# develboard.net
KiCad netlist of a schematic drawn in Altium Designer
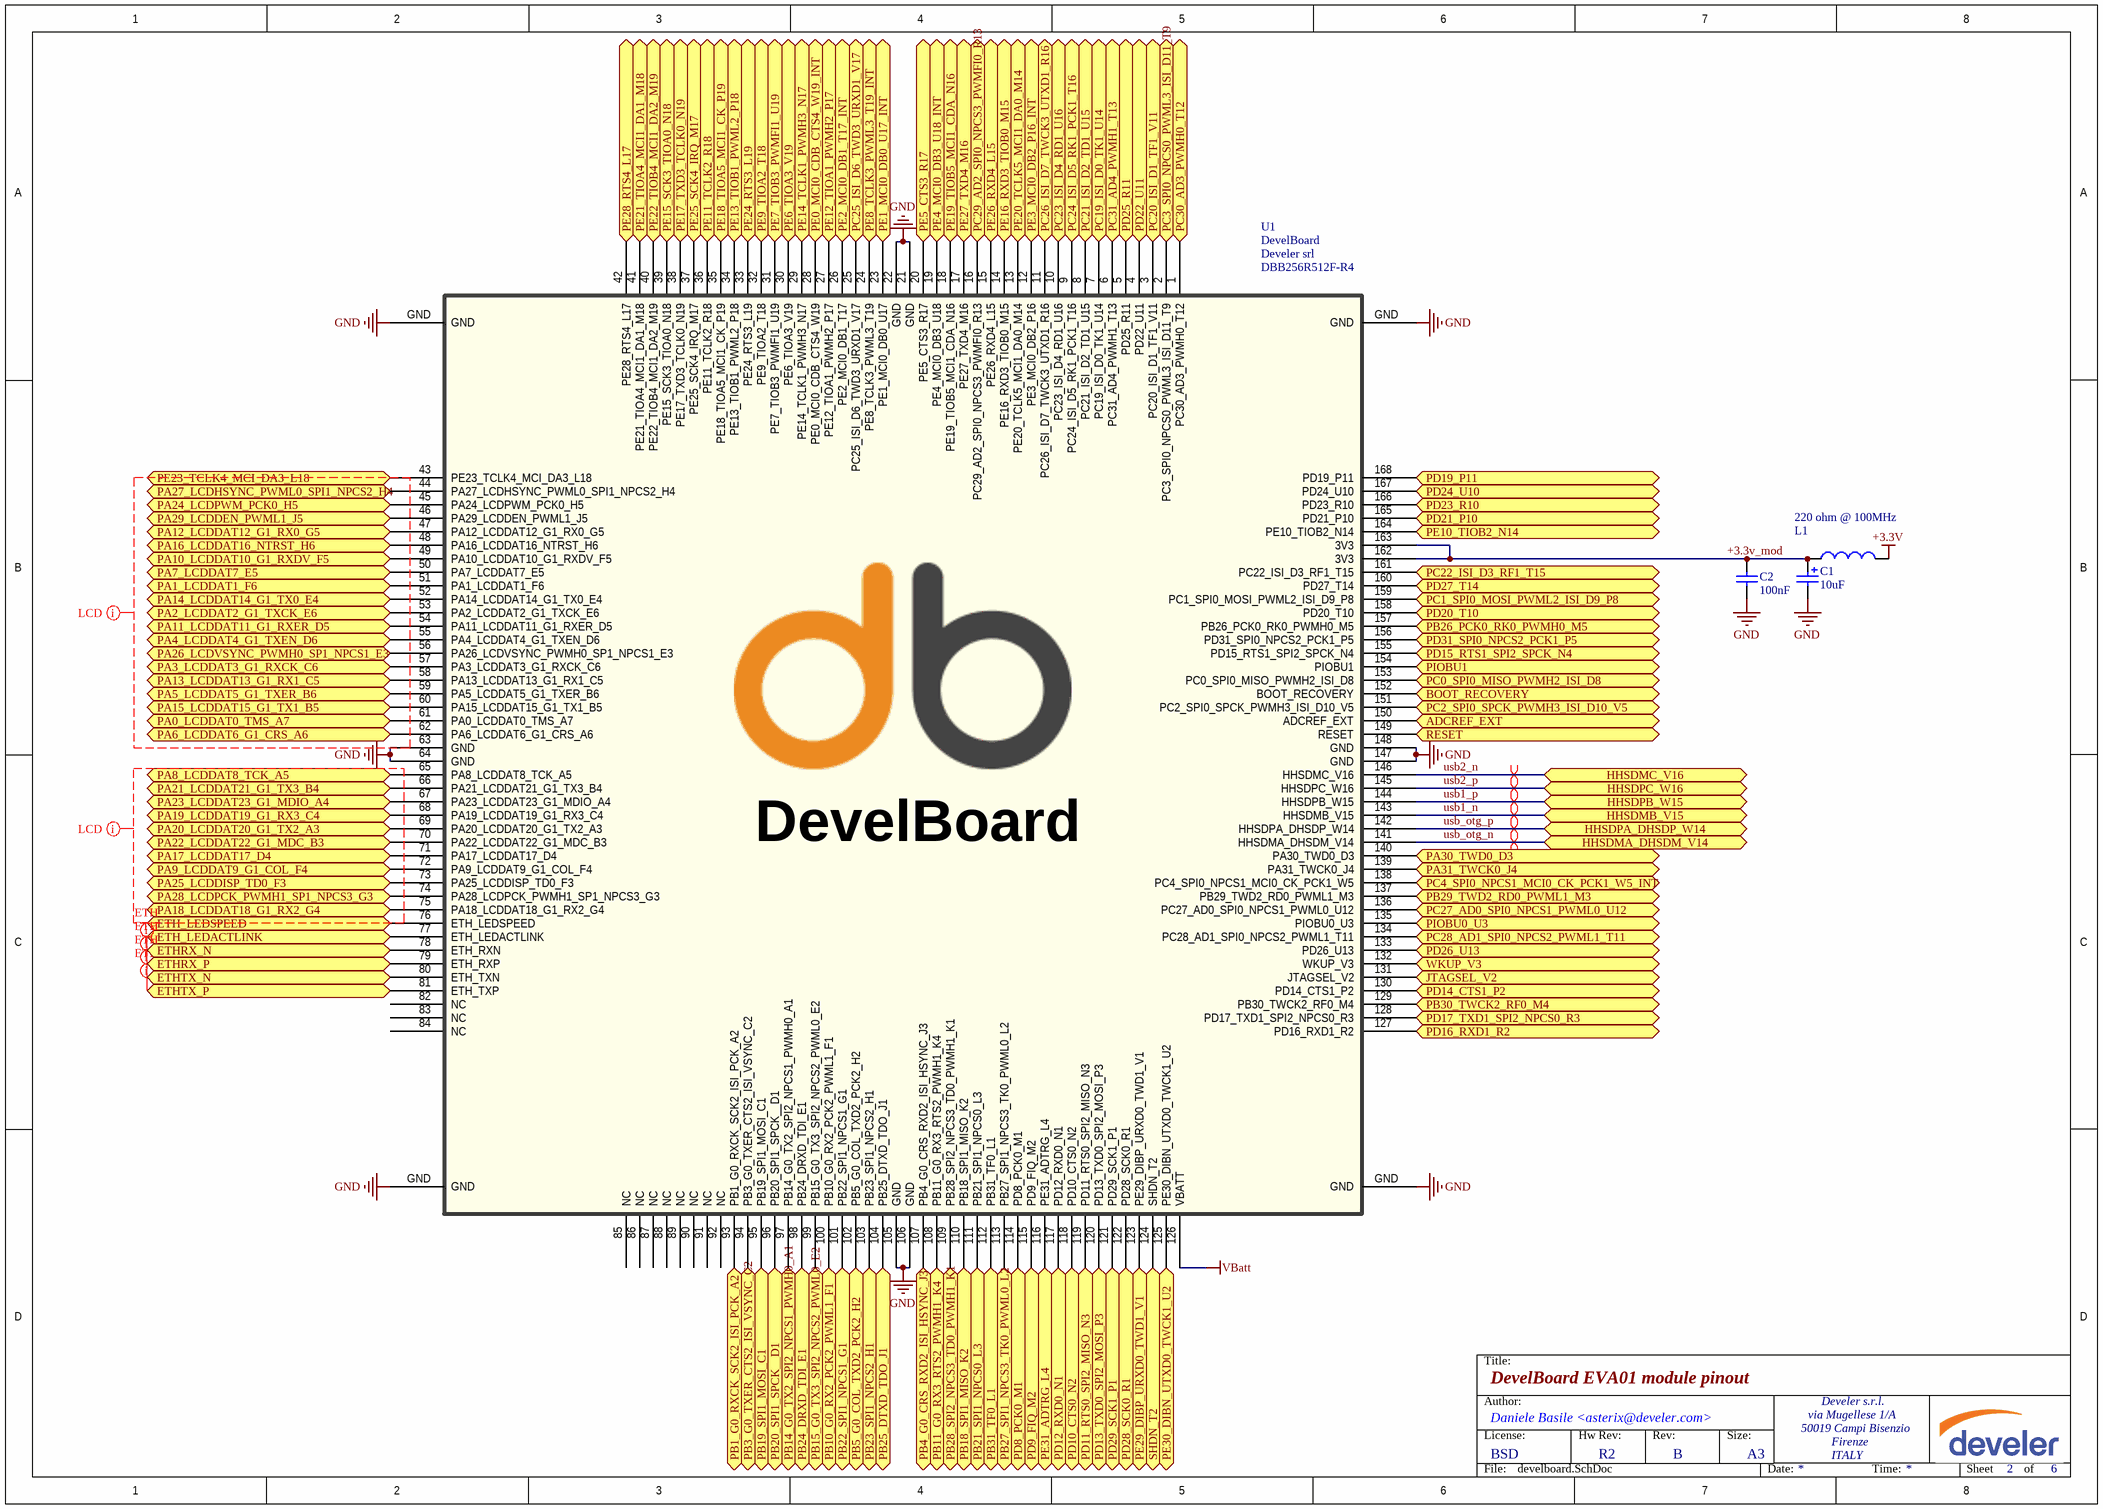
[diagram p0: develboard.SchDoc]

(export (version "E")
  (design (tool "Eeschema 10.0.6"))
  (components
    (comp (ref "C1")
      (value "10uF")
      (footprint "1206_[3216]")
      (description "Ceramic X5R 25V")
      (fields (field (name "PUBLISHER") "Altium Limited"))
      (libsource (lib "DEVELER_Library") (part "Cap Pol1"))
    )
    (comp (ref "C2")
      (value "100nF")
      (footprint "0603_[1608]")
      (description "Ceramic X7R 50V")
      (fields (field (name "PUBLISHER") "Altium Limited"))
      (libsource (lib "Miscellaneous Devices") (part "Cap"))
    )
    (comp (ref "L1")
      (value "220 ohm @ 100MHz")
      (footprint "0805_[2012]")
      (description "Ferrite Beat (WE 742792022)")
      (libsource (lib "DEVELER_Library") (part "Inductor"))
    )
    (comp (ref "U1")
      (value "DevelBoard")
      (footprint "develboard_footprint")
      (description "Faster Little Linux Module")
      (fields (field (name "COMPANY") "Develer srl") (field (name "ORDER CODE") "DBB256R512F-R4"))
      (libsource (lib "develboard_symbol") (part "develboard_pinout"))
    )
  )
  (nets
    (net (code "1") (name "+3.3V") (class "Default")
      (node (ref "L1") (pin "1") (pinfunction "1_1") (pintype "passive"))
    )
    (net (code "2") (name "/+3.3v_mod") (class "Default")
      (node (ref "C1") (pin "1") (pinfunction "1_1") (pintype "passive"))
      (node (ref "C2") (pin "1") (pinfunction "1_1") (pintype "passive"))
      (node (ref "L1") (pin "2") (pinfunction "2_2") (pintype "passive"))
      (node (ref "U1") (pin "162") (pinfunction "3V3_162") (pintype "passive"))
      (node (ref "U1") (pin "163") (pinfunction "3V3_163") (pintype "passive"))
    )
    (net (code "3") (name "/ADCREF_EXT") (class "Default")
      (node (ref "U1") (pin "150") (pinfunction "ADCREF_EXT_150") (pintype "passive"))
    )
    (net (code "4") (name "/BOOT_RECOVERY") (class "Default")
      (node (ref "U1") (pin "152") (pinfunction "BOOT_RECOVERY_152") (pintype "passive"))
    )
    (net (code "5") (name "/ETHRX_N") (class "Default")
      (node (ref "U1") (pin "78") (pinfunction "ETH_RXN_78") (pintype "passive"))
    )
    (net (code "6") (name "/ETHRX_P") (class "Default")
      (node (ref "U1") (pin "79") (pinfunction "ETH_RXP_79") (pintype "passive"))
    )
    (net (code "7") (name "/ETHTX_N") (class "Default")
      (node (ref "U1") (pin "80") (pinfunction "ETH_TXN_80") (pintype "passive"))
    )
    (net (code "8") (name "/ETHTX_P") (class "Default")
      (node (ref "U1") (pin "81") (pinfunction "ETH_TXP_81") (pintype "passive"))
    )
    (net (code "9") (name "/ETH_LEDACTLINK") (class "Default")
      (node (ref "U1") (pin "77") (pinfunction "ETH_LEDACTLINK_77") (pintype "passive"))
    )
    (net (code "10") (name "/ETH_LEDSPEED") (class "Default")
      (node (ref "U1") (pin "76") (pinfunction "ETH_LEDSPEED_76") (pintype "passive"))
    )
    (net (code "11") (name "/JTAGSEL_V2") (class "Default")
      (node (ref "U1") (pin "131") (pinfunction "JTAGSEL_V2_131") (pintype "passive"))
    )
    (net (code "12") (name "/PA0_LCDDAT0_TMS_A7") (class "Default")
      (node (ref "U1") (pin "61") (pinfunction "PA0_LCDDAT0_TMS_A7_61") (pintype "passive"))
    )
    (net (code "13") (name "/PA1_LCDDAT1_F6") (class "Default")
      (node (ref "U1") (pin "51") (pinfunction "PA1_LCDDAT1_F6_51") (pintype "passive"))
    )
    (net (code "14") (name "/PA2_LCDDAT2_G1_TXCK_E6") (class "Default")
      (node (ref "U1") (pin "53") (pinfunction "PA2_LCDDAT2_G1_TXCK_E6_53") (pintype "passive"))
    )
    (net (code "15") (name "/PA3_LCDDAT3_G1_RXCK_C6") (class "Default")
      (node (ref "U1") (pin "57") (pinfunction "PA3_LCDDAT3_G1_RXCK_C6_57") (pintype "passive"))
    )
    (net (code "16") (name "/PA4_LCDDAT4_G1_TXEN_D6") (class "Default")
      (node (ref "U1") (pin "55") (pinfunction "PA4_LCDDAT4_G1_TXEN_D6_55") (pintype "passive"))
    )
    (net (code "17") (name "/PA5_LCDDAT5_G1_TXER_B6") (class "Default")
      (node (ref "U1") (pin "59") (pinfunction "PA5_LCDDAT5_G1_TXER_B6_59") (pintype "passive"))
    )
    (net (code "18") (name "/PA6_LCDDAT6_G1_CRS_A6") (class "Default")
      (node (ref "U1") (pin "62") (pinfunction "PA6_LCDDAT6_G1_CRS_A6_62") (pintype "passive"))
    )
    (net (code "19") (name "/PA7_LCDDAT7_E5") (class "Default")
      (node (ref "U1") (pin "50") (pinfunction "PA7_LCDDAT7_E5_50") (pintype "passive"))
    )
    (net (code "20") (name "/PA8_LCDDAT8_TCK_A5") (class "Default")
      (node (ref "U1") (pin "65") (pinfunction "PA8_LCDDAT8_TCK_A5_65") (pintype "passive"))
    )
    (net (code "21") (name "/PA9_LCDDAT9_G1_COL_F4") (class "Default")
      (node (ref "U1") (pin "72") (pinfunction "PA9_LCDDAT9_G1_COL_F4_72") (pintype "passive"))
    )
    (net (code "22") (name "/PA10_LCDDAT10_G1_RXDV_F5") (class "Default")
      (node (ref "U1") (pin "49") (pinfunction "PA10_LCDDAT10_G1_RXDV_F5_49") (pintype "passive"))
    )
    (net (code "23") (name "/PA11_LCDDAT11_G1_RXER_D5") (class "Default")
      (node (ref "U1") (pin "54") (pinfunction "PA11_LCDDAT11_G1_RXER_D5_54") (pintype "passive"))
    )
    (net (code "24") (name "/PA12_LCDDAT12_G1_RX0_G5") (class "Default")
      (node (ref "U1") (pin "47") (pinfunction "PA12_LCDDAT12_G1_RX0_G5_47") (pintype "passive"))
    )
    (net (code "25") (name "/PA13_LCDDAT13_G1_RX1_C5") (class "Default")
      (node (ref "U1") (pin "58") (pinfunction "PA13_LCDDAT13_G1_RX1_C5_58") (pintype "passive"))
    )
    (net (code "26") (name "/PA14_LCDDAT14_G1_TX0_E4") (class "Default")
      (node (ref "U1") (pin "52") (pinfunction "PA14_LCDDAT14_G1_TX0_E4_52") (pintype "passive"))
    )
    (net (code "27") (name "/PA15_LCDDAT15_G1_TX1_B5") (class "Default")
      (node (ref "U1") (pin "60") (pinfunction "PA15_LCDDAT15_G1_TX1_B5_60") (pintype "passive"))
    )
    (net (code "28") (name "/PA16_LCDDAT16_NTRST_H6") (class "Default")
      (node (ref "U1") (pin "48") (pinfunction "PA16_LCDDAT16_NTRST_H6_48") (pintype "passive"))
    )
    (net (code "29") (name "/PA17_LCDDAT17_D4") (class "Default")
      (node (ref "U1") (pin "71") (pinfunction "PA17_LCDDAT17_D4_71") (pintype "passive"))
    )
    (net (code "30") (name "/PA18_LCDDAT18_G1_RX2_G4") (class "Default")
      (node (ref "U1") (pin "75") (pinfunction "PA18_LCDDAT18_G1_RX2_G4_75") (pintype "passive"))
    )
    (net (code "31") (name "/PA19_LCDDAT19_G1_RX3_C4") (class "Default")
      (node (ref "U1") (pin "68") (pinfunction "PA19_LCDDAT19_G1_RX3_C4_68") (pintype "passive"))
    )
    (net (code "32") (name "/PA20_LCDDAT20_G1_TX2_A3") (class "Default")
      (node (ref "U1") (pin "69") (pinfunction "PA20_LCDDAT20_G1_TX2_A3_69") (pintype "passive"))
    )
    (net (code "33") (name "/PA21_LCDDAT21_G1_TX3_B4") (class "Default")
      (node (ref "U1") (pin "66") (pinfunction "PA21_LCDDAT21_G1_TX3_B4_66") (pintype "passive"))
    )
    (net (code "34") (name "/PA22_LCDDAT22_G1_MDC_B3") (class "Default")
      (node (ref "U1") (pin "70") (pinfunction "PA22_LCDDAT22_G1_MDC_B3_70") (pintype "passive"))
    )
    (net (code "35") (name "/PA23_LCDDAT23_G1_MDIO_A4") (class "Default")
      (node (ref "U1") (pin "67") (pinfunction "PA23_LCDDAT23_G1_MDIO_A4_67") (pintype "passive"))
    )
    (net (code "36") (name "/PA24_LCDPWM_PCK0_H5") (class "Default")
      (node (ref "U1") (pin "45") (pinfunction "PA24_LCDPWM_PCK0_H5_45") (pintype "passive"))
    )
    (net (code "37") (name "/PA25_LCDDISP_TD0_F3") (class "Default")
      (node (ref "U1") (pin "73") (pinfunction "PA25_LCDDISP_TD0_F3_73") (pintype "passive"))
    )
    (net (code "38") (name "/PA26_LCDVSYNC_PWMH0_SP1_NPCS1_E3") (class "Default")
      (node (ref "U1") (pin "56") (pinfunction "PA26_LCDVSYNC_PWMH0_SP1_NPCS1_E3_56") (pintype "passive"))
    )
    (net (code "39") (name "/PA27_LCDHSYNC_PWML0_SPI1_NPCS2_H4") (class "Default")
      (node (ref "U1") (pin "44") (pinfunction "PA27_LCDHSYNC_PWML0_SPI1_NPCS2_H4_44") (pintype "passive"))
    )
    (net (code "40") (name "/PA28_LCDPCK_PWMH1_SP1_NPCS3_G3") (class "Default")
      (node (ref "U1") (pin "74") (pinfunction "PA28_LCDPCK_PWMH1_SP1_NPCS3_G3_74") (pintype "passive"))
    )
    (net (code "41") (name "/PA29_LCDDEN_PWML1_J5") (class "Default")
      (node (ref "U1") (pin "46") (pinfunction "PA29_LCDDEN_PWML1_J5_46") (pintype "passive"))
    )
    (net (code "42") (name "/PA30_TWD0_D3") (class "Default")
      (node (ref "U1") (pin "140") (pinfunction "PA30_TWD0_D3_140") (pintype "passive"))
    )
    (net (code "43") (name "/PA31_TWCK0_J4") (class "Default")
      (node (ref "U1") (pin "139") (pinfunction "PA31_TWCK0_J4_139") (pintype "passive"))
    )
    (net (code "44") (name "/PB1_G0_RXCK_SCK2_ISI_PCK_A2") (class "Default")
      (node (ref "U1") (pin "93") (pinfunction "PB1_G0_RXCK_SCK2_ISI_PCK_A2_93") (pintype "passive"))
    )
    (net (code "45") (name "/PB3_G0_TXER_CTS2_ISI_VSYNC_C2") (class "Default")
      (node (ref "U1") (pin "94") (pinfunction "PB3_G0_TXER_CTS2_ISI_VSYNC_C2_94") (pintype "passive"))
    )
    (net (code "46") (name "/PB4_G0_CRS_RXD2_ISI_HSYNC_J3") (class "Default")
      (node (ref "U1") (pin "107") (pinfunction "PB4_G0_CRS_RXD2_ISI_HSYNC_J3_107") (pintype "passive"))
    )
    (net (code "47") (name "/PB5_G0_COL_TXD2_PCK2_H2") (class "Default")
      (node (ref "U1") (pin "102") (pinfunction "PB5_G0_COL_TXD2_PCK2_H2_102") (pintype "passive"))
    )
    (net (code "48") (name "/PB10_G0_RX2_PCK2_PWML1_F1") (class "Default")
      (node (ref "U1") (pin "100") (pinfunction "PB10_G0_RX2_PCK2_PWML1_F1_100") (pintype "passive"))
    )
    (net (code "49") (name "/PB11_G0_RX3_RTS2_PWMH1_K4") (class "Default")
      (node (ref "U1") (pin "108") (pinfunction "PB11_G0_RX3_RTS2_PWMH1_K4_108") (pintype "passive"))
    )
    (net (code "50") (name "/PB14_G0_TX2_SPI2_NPCS1_PWMH0_A1") (class "Default")
      (node (ref "U1") (pin "97") (pinfunction "PB14_G0_TX2_SPI2_NPCS1_PWMH0_A1_97") (pintype "passive"))
    )
    (net (code "51") (name "/PB15_G0_TX3_SPI2_NPCS2_PWML0_E2") (class "Default")
      (node (ref "U1") (pin "99") (pinfunction "PB15_G0_TX3_SPI2_NPCS2_PWML0_E2_99") (pintype "passive"))
    )
    (net (code "52") (name "/PB18_SPI1_MISO_K2") (class "Default")
      (node (ref "U1") (pin "110") (pinfunction "PB18_SPI1_MISO_K2_110") (pintype "passive"))
    )
    (net (code "53") (name "/PB19_SPI1_MOSI_C1") (class "Default")
      (node (ref "U1") (pin "95") (pinfunction "PB19_SPI1_MOSI_C1_95") (pintype "passive"))
    )
    (net (code "54") (name "/PB20_SPI1_SPCK__D1") (class "Default")
      (node (ref "U1") (pin "96") (pinfunction "PB20_SPI1_SPCK__D1_96") (pintype "passive"))
    )
    (net (code "55") (name "/PB21_SPI1_NPCS0_L3") (class "Default")
      (node (ref "U1") (pin "111") (pinfunction "PB21_SPI1_NPCS0_L3_111") (pintype "passive"))
    )
    (net (code "56") (name "/PB22_SPI1_NPCS1_G1") (class "Default")
      (node (ref "U1") (pin "101") (pinfunction "PB22_SPI1_NPCS1_G1_101") (pintype "passive"))
    )
    (net (code "57") (name "/PB23_SPI1_NPCS2_H1") (class "Default")
      (node (ref "U1") (pin "103") (pinfunction "PB23_SPI1_NPCS2_H1_103") (pintype "passive"))
    )
    (net (code "58") (name "/PB24_DRXD_TDI_E1") (class "Default")
      (node (ref "U1") (pin "98") (pinfunction "PB24_DRXD_TDI_E1_98") (pintype "passive"))
    )
    (net (code "59") (name "/PB25_DTXD_TDO_J1") (class "Default")
      (node (ref "U1") (pin "104") (pinfunction "PB25_DTXD_TDO_J1_104") (pintype "passive"))
    )
    (net (code "60") (name "/PB26_PCK0_RK0_PWMH0_M5") (class "Default")
      (node (ref "U1") (pin "157") (pinfunction "PB26_PCK0_RK0_PWMH0_M5_157") (pintype "passive"))
    )
    (net (code "61") (name "/PB27_SPI1_NPCS3_TK0_PWML0_L2") (class "Default")
      (node (ref "U1") (pin "113") (pinfunction "PB27_SPI1_NPCS3_TK0_PWML0_L2_113") (pintype "passive"))
    )
    (net (code "62") (name "/PB28_SPI2_NPCS3_TD0_PWMH1_K1") (class "Default")
      (node (ref "U1") (pin "109") (pinfunction "PB28_SPI2_NPCS3_TD0_PWMH1_K1_109") (pintype "passive"))
    )
    (net (code "63") (name "/PB29_TWD2_RD0_PWML1_M3") (class "Default")
      (node (ref "U1") (pin "137") (pinfunction "PB29_TWD2_RD0_PWML1_M3_137") (pintype "passive"))
    )
    (net (code "64") (name "/PB30_TWCK2_RF0_M4") (class "Default")
      (node (ref "U1") (pin "129") (pinfunction "PB30_TWCK2_RF0_M4_129") (pintype "passive"))
    )
    (net (code "65") (name "/PB31_TF0_L1") (class "Default")
      (node (ref "U1") (pin "112") (pinfunction "PB31_TF0_L1_112") (pintype "passive"))
    )
    (net (code "66") (name "/PC0_SPI0_MISO_PWMH2_ISI_D8") (class "Default")
      (node (ref "U1") (pin "153") (pinfunction "PC0_SPI0_MISO_PWMH2_ISI_D8_153") (pintype "passive"))
    )
    (net (code "67") (name "/PC1_SPI0_MOSI_PWML2_ISI_D9_P8") (class "Default")
      (node (ref "U1") (pin "159") (pinfunction "PC1_SPI0_MOSI_PWML2_ISI_D9_P8_159") (pintype "passive"))
    )
    (net (code "68") (name "/PC2_SPI0_SPCK_PWMH3_ISI_D10_V5") (class "Default")
      (node (ref "U1") (pin "151") (pinfunction "PC2_SPI0_SPCK_PWMH3_ISI_D10_V5_151") (pintype "passive"))
    )
    (net (code "69") (name "/PC3_SPI0_NPCS0_PWML3_ISI_D11_T9") (class "Default")
      (node (ref "U1") (pin "2") (pinfunction "PC3_SPI0_NPCS0_PWML3_ISI_D11_T9_2") (pintype "passive"))
    )
    (net (code "70") (name "/PC4_SPI0_NPCS1_MCI0_CK_PCK1_W5_INT") (class "Default")
      (node (ref "U1") (pin "138") (pinfunction "PC4_SPI0_NPCS1_MCI0_CK_PCK1_W5_138") (pintype "passive"))
    )
    (net (code "71") (name "/PC19_ISI_D0_TK1_U14") (class "Default")
      (node (ref "U1") (pin "7") (pinfunction "PC19_ISI_D0_TK1_U14_7") (pintype "passive"))
    )
    (net (code "72") (name "/PC20_ISI_D1_TF1_V11") (class "Default")
      (node (ref "U1") (pin "3") (pinfunction "PC20_ISI_D1_TF1_V11_3") (pintype "passive"))
    )
    (net (code "73") (name "/PC21_ISI_D2_TD1_U15") (class "Default")
      (node (ref "U1") (pin "8") (pinfunction "PC21_ISI_D2_TD1_U15_8") (pintype "passive"))
    )
    (net (code "74") (name "/PC22_ISI_D3_RF1_T15") (class "Default")
      (node (ref "U1") (pin "161") (pinfunction "PC22_ISI_D3_RF1_T15_161") (pintype "passive"))
    )
    (net (code "75") (name "/PC23_ISI_D4_RD1_U16") (class "Default")
      (node (ref "U1") (pin "10") (pinfunction "PC23_ISI_D4_RD1_U16_10") (pintype "passive"))
    )
    (net (code "76") (name "/PC24_ISI_D5_RK1_PCK1_T16") (class "Default")
      (node (ref "U1") (pin "9") (pinfunction "PC24_ISI_D5_RK1_PCK1_T16_9") (pintype "passive"))
    )
    (net (code "77") (name "/PC25_ISI_D6_TWD3_URXD1_V17") (class "Default")
      (node (ref "U1") (pin "25") (pinfunction "PC25_ISI_D6_TWD3_URXD1_V17_25") (pintype "passive"))
    )
    (net (code "78") (name "/PC26_ISI_D7_TWCK3_UTXD1_R16") (class "Default")
      (node (ref "U1") (pin "11") (pinfunction "PC26_ISI_D7_TWCK3_UTXD1_R16_11") (pintype "passive"))
    )
    (net (code "79") (name "/PC27_AD0_SPI0_NPCS1_PWML0_U12") (class "Default")
      (node (ref "U1") (pin "136") (pinfunction "PC27_AD0_SPI0_NPCS1_PWML0_U12_136") (pintype "passive"))
    )
    (net (code "80") (name "/PC28_AD1_SPI0_NPCS2_PWML1_T11") (class "Default")
      (node (ref "U1") (pin "134") (pinfunction "PC28_AD1_SPI0_NPCS2_PWML1_T11_134") (pintype "passive"))
    )
    (net (code "81") (name "/PC29_AD2_SPI0_NPCS3_PWMFI0_R13") (class "Default")
      (node (ref "U1") (pin "16") (pinfunction "PC29_AD2_SPI0_NPCS3_PWMFI0_R13_16") (pintype "passive"))
    )
    (net (code "82") (name "/PC30_AD3_PWMH0_T12") (class "Default")
      (node (ref "U1") (pin "1") (pinfunction "PC30_AD3_PWMH0_T12_1") (pintype "passive"))
    )
    (net (code "83") (name "/PC31_AD4_PWMH1_T13") (class "Default")
      (node (ref "U1") (pin "6") (pinfunction "PC31_AD4_PWMH1_T13_6") (pintype "passive"))
    )
    (net (code "84") (name "/PD8_PCK0_M1") (class "Default")
      (node (ref "U1") (pin "114") (pinfunction "PD8_PCK0_M1_114") (pintype "passive"))
    )
    (net (code "85") (name "/PD9_FIQ_M2") (class "Default")
      (node (ref "U1") (pin "115") (pinfunction "PD9_FIQ_M2_115") (pintype "passive"))
    )
    (net (code "86") (name "/PD10_CTS0_N2") (class "Default")
      (node (ref "U1") (pin "118") (pinfunction "PD10_CTS0_N2_118") (pintype "passive"))
    )
    (net (code "87") (name "/PD11_RTS0_SPI2_MISO_N3") (class "Default")
      (node (ref "U1") (pin "119") (pinfunction "PD11_RTS0_SPI2_MISO_N3_119") (pintype "passive"))
    )
    (net (code "88") (name "/PD12_RXD0_N1") (class "Default")
      (node (ref "U1") (pin "117") (pinfunction "PD12_RXD0_N1_117") (pintype "passive"))
    )
    (net (code "89") (name "/PD13_TXD0_SPI2_MOSI_P3") (class "Default")
      (node (ref "U1") (pin "120") (pinfunction "PD13_TXD0_SPI2_MOSI_P3_120") (pintype "passive"))
    )
    (net (code "90") (name "/PD14_CTS1_P2") (class "Default")
      (node (ref "U1") (pin "130") (pinfunction "PD14_CTS1_P2_130") (pintype "passive"))
    )
    (net (code "91") (name "/PD15_RTS1_SPI2_SPCK_N4") (class "Default")
      (node (ref "U1") (pin "155") (pinfunction "PD15_RTS1_SPI2_SPCK_N4_155") (pintype "passive"))
    )
    (net (code "92") (name "/PD16_RXD1_R2") (class "Default")
      (node (ref "U1") (pin "127") (pinfunction "PD16_RXD1_R2_127") (pintype "passive"))
    )
    (net (code "93") (name "/PD17_TXD1_SPI2_NPCS0_R3") (class "Default")
      (node (ref "U1") (pin "128") (pinfunction "PD17_TXD1_SPI2_NPCS0_R3_128") (pintype "passive"))
    )
    (net (code "94") (name "/PD19_P11") (class "Default")
      (node (ref "U1") (pin "168") (pinfunction "PD19_P11_168") (pintype "passive"))
    )
    (net (code "95") (name "/PD20_T10") (class "Default")
      (node (ref "U1") (pin "158") (pinfunction "PD20_T10_158") (pintype "passive"))
    )
    (net (code "96") (name "/PD21_P10") (class "Default")
      (node (ref "U1") (pin "165") (pinfunction "PD21_P10_165") (pintype "passive"))
    )
    (net (code "97") (name "/PD22_U11") (class "Default")
      (node (ref "U1") (pin "4") (pinfunction "PD22_U11_4") (pintype "passive"))
    )
    (net (code "98") (name "/PD23_R10") (class "Default")
      (node (ref "U1") (pin "166") (pinfunction "PD23_R10_166") (pintype "passive"))
    )
    (net (code "99") (name "/PD24_U10") (class "Default")
      (node (ref "U1") (pin "167") (pinfunction "PD24_U10_167") (pintype "passive"))
    )
    (net (code "100") (name "/PD25_R11") (class "Default")
      (node (ref "U1") (pin "5") (pinfunction "PD25_R11_5") (pintype "passive"))
    )
    (net (code "101") (name "/PD26_U13") (class "Default")
      (node (ref "U1") (pin "133") (pinfunction "PD26_U13_133") (pintype "passive"))
    )
    (net (code "102") (name "/PD27_T14") (class "Default")
      (node (ref "U1") (pin "160") (pinfunction "PD27_T14_160") (pintype "passive"))
    )
    (net (code "103") (name "/PD28_SCK0_R1") (class "Default")
      (node (ref "U1") (pin "122") (pinfunction "PD28_SCK0_R1_122") (pintype "passive"))
    )
    (net (code "104") (name "/PD29_SCK1_P1") (class "Default")
      (node (ref "U1") (pin "121") (pinfunction "PD29_SCK1_P1_121") (pintype "passive"))
    )
    (net (code "105") (name "/PD31_SPI0_NPCS2_PCK1_P5") (class "Default")
      (node (ref "U1") (pin "156") (pinfunction "PD31_SPI0_NPCS2_PCK1_P5_156") (pintype "passive"))
    )
    (net (code "106") (name "/PE0_MCI0_CDB_CTS4_W19_INT") (class "Default")
      (node (ref "U1") (pin "28") (pinfunction "PE0_MCI0_CDB_CTS4_W19_28") (pintype "passive"))
    )
    (net (code "107") (name "/PE1_MCI0_DB0_U17_INT") (class "Default")
      (node (ref "U1") (pin "23") (pinfunction "PE1_MCI0_DB0_U17_23") (pintype "passive"))
    )
    (net (code "108") (name "/PE2_MCI0_DB1_T17_INT") (class "Default")
      (node (ref "U1") (pin "26") (pinfunction "PE2_MCI0_DB1_T17_26") (pintype "passive"))
    )
    (net (code "109") (name "/PE3_MCI0_DB2_P16_INT") (class "Default")
      (node (ref "U1") (pin "12") (pinfunction "PE3_MCI0_DB2_P16_12") (pintype "passive"))
    )
    (net (code "110") (name "/PE4_MCI0_DB3_U18_INT") (class "Default")
      (node (ref "U1") (pin "19") (pinfunction "PE4_MCI0_DB3_U18_19") (pintype "passive"))
    )
    (net (code "111") (name "/PE5_CTS3_R17") (class "Default")
      (node (ref "U1") (pin "20") (pinfunction "PE5_CTS3_R17_20") (pintype "passive"))
    )
    (net (code "112") (name "/PE6_TIOA3_V19") (class "Default")
      (node (ref "U1") (pin "30") (pinfunction "PE6_TIOA3_V19_30") (pintype "passive"))
    )
    (net (code "113") (name "/PE7_TIOB3_PWMFI1_U19") (class "Default")
      (node (ref "U1") (pin "31") (pinfunction "PE7_TIOB3_PWMFI1_U19_31") (pintype "passive"))
    )
    (net (code "114") (name "/PE8_TCLK3_PWML3_T19_INT") (class "Default")
      (node (ref "U1") (pin "24") (pinfunction "PE8_TCLK3_PWML3_T19_24") (pintype "passive"))
    )
    (net (code "115") (name "/PE9_TIOA2_T18") (class "Default")
      (node (ref "U1") (pin "32") (pinfunction "PE9_TIOA2_T18_32") (pintype "passive"))
    )
    (net (code "116") (name "/PE10_TIOB2_N14") (class "Default")
      (node (ref "U1") (pin "164") (pinfunction "PE10_TIOB2_N14_164") (pintype "passive"))
    )
    (net (code "117") (name "/PE11_TCLK2_R18") (class "Default")
      (node (ref "U1") (pin "36") (pinfunction "PE11_TCLK2_R18_36") (pintype "passive"))
    )
    (net (code "118") (name "/PE12_TIOA1_PWMH2_P17") (class "Default")
      (node (ref "U1") (pin "27") (pinfunction "PE12_TIOA1_PWMH2_P17_27") (pintype "passive"))
    )
    (net (code "119") (name "/PE13_TIOB1_PWML2_P18") (class "Default")
      (node (ref "U1") (pin "34") (pinfunction "PE13_TIOB1_PWML2_P18_34") (pintype "passive"))
    )
    (net (code "120") (name "/PE14_TCLK1_PWMH3_N17") (class "Default")
      (node (ref "U1") (pin "29") (pinfunction "PE14_TCLK1_PWMH3_N17_29") (pintype "passive"))
    )
    (net (code "121") (name "/PE15_SCK3_TIOA0_N18") (class "Default")
      (node (ref "U1") (pin "39") (pinfunction "PE15_SCK3_TIOA0_N18_39") (pintype "passive"))
    )
    (net (code "122") (name "/PE16_RXD3_TIOB0_M15") (class "Default")
      (node (ref "U1") (pin "14") (pinfunction "PE16_RXD3_TIOB0_M15_14") (pintype "passive"))
    )
    (net (code "123") (name "/PE17_TXD3_TCLK0_N19") (class "Default")
      (node (ref "U1") (pin "38") (pinfunction "PE17_TXD3_TCLK0_N19_38") (pintype "passive"))
    )
    (net (code "124") (name "/PE18_TIOA5_MCI1_CK_P19") (class "Default")
      (node (ref "U1") (pin "35") (pinfunction "PE18_TIOA5_MCI1_CK_P19_35") (pintype "passive"))
    )
    (net (code "125") (name "/PE19_TIOB5_MCI1_CDA_N16") (class "Default")
      (node (ref "U1") (pin "18") (pinfunction "PE19_TIOB5_MCI1_CDA_N16_18") (pintype "passive"))
    )
    (net (code "126") (name "/PE20_TCLK5_MCI1_DA0_M14") (class "Default")
      (node (ref "U1") (pin "13") (pinfunction "PE20_TCLK5_MCI1_DA0_M14_13") (pintype "passive"))
    )
    (net (code "127") (name "/PE21_TIOA4_MCI1_DA1_M18") (class "Default")
      (node (ref "U1") (pin "41") (pinfunction "PE21_TIOA4_MCI1_DA1_M18_41") (pintype "passive"))
    )
    (net (code "128") (name "/PE22_TIOB4_MCI1_DA2_M19") (class "Default")
      (node (ref "U1") (pin "40") (pinfunction "PE22_TIOB4_MCI1_DA2_M19_40") (pintype "passive"))
    )
    (net (code "129") (name "/PE23_TCLK4_MCI_DA3_L18") (class "Default")
      (node (ref "U1") (pin "43") (pinfunction "PE23_TCLK4_MCI_DA3_L18_43") (pintype "passive"))
    )
    (net (code "130") (name "/PE24_RTS3_L19") (class "Default")
      (node (ref "U1") (pin "33") (pinfunction "PE24_RTS3_L19_33") (pintype "passive"))
    )
    (net (code "131") (name "/PE25_SCK4_IRQ_M17") (class "Default")
      (node (ref "U1") (pin "37") (pinfunction "PE25_SCK4_IRQ_M17_37") (pintype "passive"))
    )
    (net (code "132") (name "/PE26_RXD4_L15") (class "Default")
      (node (ref "U1") (pin "15") (pinfunction "PE26_RXD4_L15_15") (pintype "passive"))
    )
    (net (code "133") (name "/PE27_TXD4_M16") (class "Default")
      (node (ref "U1") (pin "17") (pinfunction "PE27_TXD4_M16_17") (pintype "passive"))
    )
    (net (code "134") (name "/PE28_RTS4_L17") (class "Default")
      (node (ref "U1") (pin "42") (pinfunction "PE28_RTS4_L17_42") (pintype "passive"))
    )
    (net (code "135") (name "/PE29_DIBP_URXD0_TWD1_V1") (class "Default")
      (node (ref "U1") (pin "123") (pinfunction "PE29_DIBP_URXD0_TWD1_V1_123") (pintype "passive"))
    )
    (net (code "136") (name "/PE30_DIBN_UTXD0_TWCK1_U2") (class "Default")
      (node (ref "U1") (pin "125") (pinfunction "PE30_DIBN_UTXD0_TWCK1_U2_125") (pintype "passive"))
    )
    (net (code "137") (name "/PE31_ADTRG_L4") (class "Default")
      (node (ref "U1") (pin "116") (pinfunction "PE31_ADTRG_L4_116") (pintype "passive"))
    )
    (net (code "138") (name "/PIOBU0_U3") (class "Default")
      (node (ref "U1") (pin "135") (pinfunction "PIOBU0_U3_135") (pintype "passive"))
    )
    (net (code "139") (name "/PIOBU1") (class "Default")
      (node (ref "U1") (pin "154") (pinfunction "PIOBU1_154") (pintype "passive"))
    )
    (net (code "140") (name "/RESET") (class "Default")
      (node (ref "U1") (pin "149") (pinfunction "RESET_149") (pintype "passive"))
    )
    (net (code "141") (name "/SHDN_T2") (class "Default")
      (node (ref "U1") (pin "124") (pinfunction "SHDN_T2_124") (pintype "passive"))
    )
    (net (code "142") (name "/WKUP_V3") (class "Default")
      (node (ref "U1") (pin "132") (pinfunction "WKUP_V3_132") (pintype "passive"))
    )
    (net (code "143") (name "/usb1_n") (class "Default")
      (node (ref "U1") (pin "143") (pinfunction "HHSDMB_V15_143") (pintype "passive"))
    )
    (net (code "144") (name "/usb1_p") (class "Default")
      (node (ref "U1") (pin "144") (pinfunction "HHSDPB_W15_144") (pintype "passive"))
    )
    (net (code "145") (name "/usb2_n") (class "Default")
      (node (ref "U1") (pin "146") (pinfunction "HHSDMC_V16_146") (pintype "passive"))
    )
    (net (code "146") (name "/usb2_p") (class "Default")
      (node (ref "U1") (pin "145") (pinfunction "HHSDPC_W16_145") (pintype "passive"))
    )
    (net (code "147") (name "/usb_otg_n") (class "Default")
      (node (ref "U1") (pin "141") (pinfunction "HHSDMA_DHSDM_V14_141") (pintype "passive"))
    )
    (net (code "148") (name "/usb_otg_p") (class "Default")
      (node (ref "U1") (pin "142") (pinfunction "HHSDPA_DHSDP_W14_142") (pintype "passive"))
    )
    (net (code "149") (name "GND") (class "Default")
      (node (ref "C1") (pin "2") (pinfunction "2_2") (pintype "passive"))
      (node (ref "C2") (pin "2") (pinfunction "2_2") (pintype "passive"))
      (node (ref "U1") (pin "105") (pinfunction "GND_105") (pintype "passive"))
      (node (ref "U1") (pin "106") (pinfunction "GND_106") (pintype "passive"))
      (node (ref "U1") (pin "147") (pinfunction "GND_147") (pintype "passive"))
      (node (ref "U1") (pin "148") (pinfunction "GND_148") (pintype "passive"))
      (node (ref "U1") (pin "21") (pinfunction "GND_21") (pintype "passive"))
      (node (ref "U1") (pin "22") (pinfunction "GND_22") (pintype "passive"))
      (node (ref "U1") (pin "63") (pinfunction "GND_63") (pintype "passive"))
      (node (ref "U1") (pin "64") (pinfunction "GND_64") (pintype "passive"))
      (node (ref "U1") (pin "GND") (pinfunction "GND_GND") (pintype "passive"))
    )
    (net (code "150") (name "VBatt") (class "Default")
      (node (ref "U1") (pin "126") (pinfunction "VBATT_126") (pintype "passive"))
    )
    (net (code "151") (name "unconnected-(U1-NC-Pad82)") (class "Default")
      (node (ref "U1") (pin "82") (pinfunction "NC_82") (pintype "passive"))
    )
    (net (code "152") (name "unconnected-(U1-NC-Pad83)") (class "Default")
      (node (ref "U1") (pin "83") (pinfunction "NC_83") (pintype "passive"))
    )
    (net (code "153") (name "unconnected-(U1-NC-Pad84)") (class "Default")
      (node (ref "U1") (pin "84") (pinfunction "NC_84") (pintype "passive"))
    )
    (net (code "154") (name "unconnected-(U1-NC-Pad85)") (class "Default")
      (node (ref "U1") (pin "85") (pinfunction "NC_85") (pintype "passive"))
    )
    (net (code "155") (name "unconnected-(U1-NC-Pad86)") (class "Default")
      (node (ref "U1") (pin "86") (pinfunction "NC_86") (pintype "passive"))
    )
    (net (code "156") (name "unconnected-(U1-NC-Pad87)") (class "Default")
      (node (ref "U1") (pin "87") (pinfunction "NC_87") (pintype "passive"))
    )
    (net (code "157") (name "unconnected-(U1-NC-Pad88)") (class "Default")
      (node (ref "U1") (pin "88") (pinfunction "NC_88") (pintype "passive"))
    )
    (net (code "158") (name "unconnected-(U1-NC-Pad89)") (class "Default")
      (node (ref "U1") (pin "89") (pinfunction "NC_89") (pintype "passive"))
    )
    (net (code "159") (name "unconnected-(U1-NC-Pad90)") (class "Default")
      (node (ref "U1") (pin "90") (pinfunction "NC_90") (pintype "passive"))
    )
    (net (code "160") (name "unconnected-(U1-NC-Pad91)") (class "Default")
      (node (ref "U1") (pin "91") (pinfunction "NC_91") (pintype "passive"))
    )
    (net (code "161") (name "unconnected-(U1-NC-Pad92)") (class "Default")
      (node (ref "U1") (pin "92") (pinfunction "NC_92") (pintype "passive"))
    )
  )
)
